# FAN-zero30-SHIM.net
KiCad netlist of a schematic drawn in EAGLE
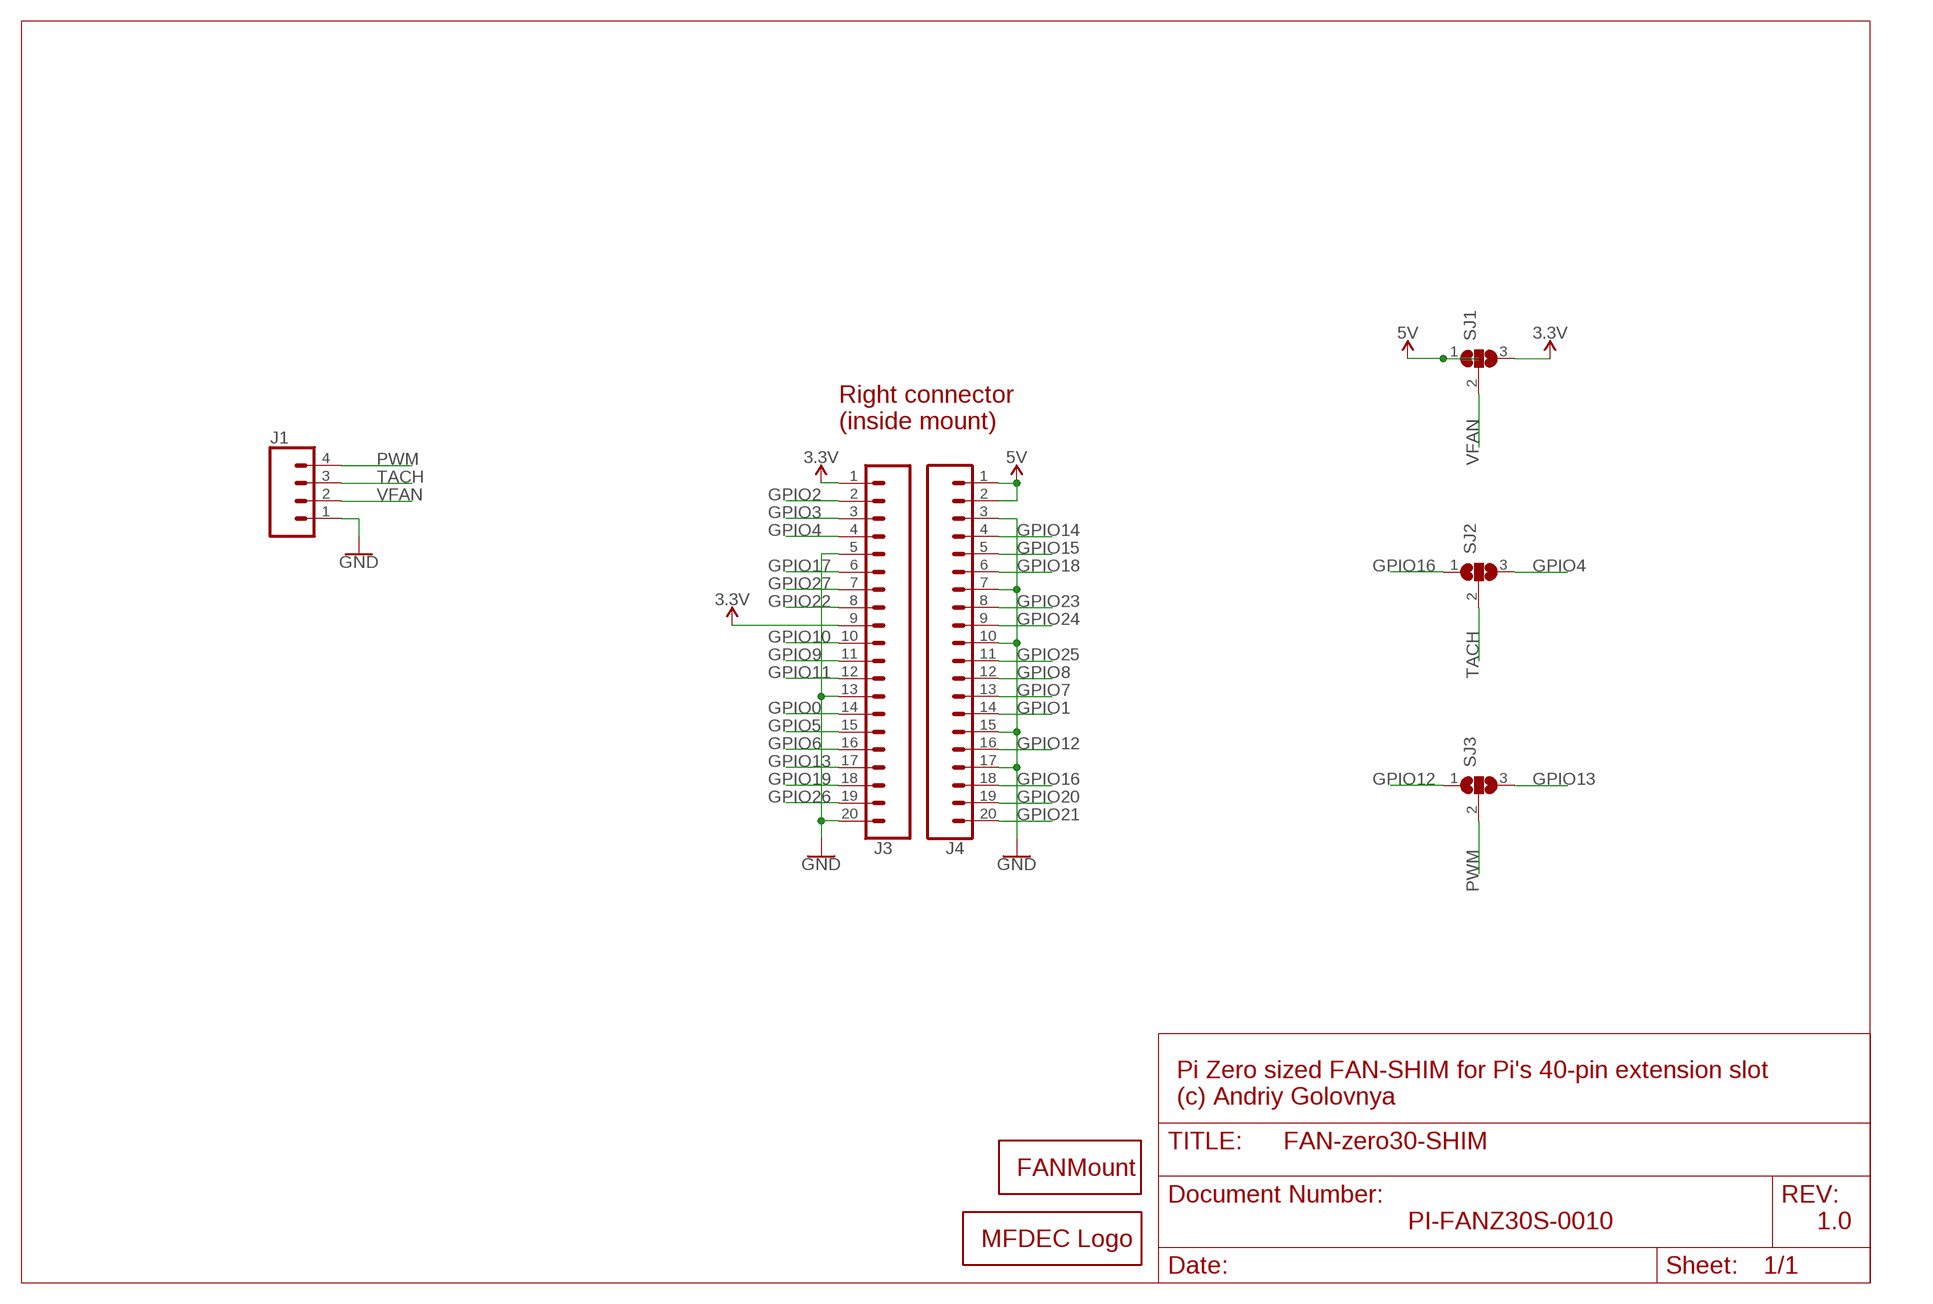
[diagram p0: schematic, sheet 1]

(export (version "E")
  (design (tool "Eeschema 10.0.6"))
  (components
    (comp (ref "FAN1")
      (value "FAN30HO")
      (footprint "eagle-import:FAN30HO")
      (libsource (lib "eagle-import") (part "FAN30HO"))
    )
    (comp (ref "J1")
      (value "CONN_04")
      (footprint "eagle-import:1X04")
      (libsource (lib "eagle-import") (part "CONN_04"))
    )
    (comp (ref "J3")
      (value "CONN_20LOCK")
      (footprint "eagle-import:1X20_LOCK")
      (libsource (lib "eagle-import") (part "CONN_20LOCK"))
    )
    (comp (ref "J4")
      (value "CONN_20LOCK")
      (footprint "eagle-import:1X20_LOCK")
      (libsource (lib "eagle-import") (part "CONN_20LOCK"))
    )
    (comp (ref "LOGO1")
      (value "MFDECLOGO_L_30MM")
      (footprint "eagle-import:MFDEC_L_30MM")
      (libsource (lib "eagle-import") (part "MFDECLOGO_L_30MM"))
    )
    (comp (ref "SJ1")
      (value "SJ2")
      (footprint "eagle-import:SJ_2")
      (libsource (lib "eagle-import") (part "SJ2"))
    )
    (comp (ref "SJ2")
      (value "SJ2")
      (footprint "eagle-import:SJ_2")
      (libsource (lib "eagle-import") (part "SJ2"))
    )
    (comp (ref "SJ3")
      (value "SJ2")
      (footprint "eagle-import:SJ_2")
      (libsource (lib "eagle-import") (part "SJ2"))
    )
  )
  (nets
    (net (code "1") (name "/GPIO0") (class "Default")
      (node (ref "J3") (pin "14") (pinfunction "14_14") (pintype "passive"))
    )
    (net (code "2") (name "/GPIO1") (class "Default")
      (node (ref "J4") (pin "14") (pinfunction "14_14") (pintype "passive"))
    )
    (net (code "3") (name "/GPIO2") (class "Default")
      (node (ref "J3") (pin "2") (pinfunction "2_2") (pintype "passive"))
    )
    (net (code "4") (name "/GPIO3") (class "Default")
      (node (ref "J3") (pin "3") (pinfunction "3_3") (pintype "passive"))
    )
    (net (code "5") (name "/GPIO4") (class "Default")
      (node (ref "J3") (pin "4") (pinfunction "4_4") (pintype "passive"))
      (node (ref "SJ2") (pin "3") (pinfunction "3_3") (pintype "passive"))
    )
    (net (code "6") (name "/GPIO5") (class "Default")
      (node (ref "J3") (pin "15") (pinfunction "15_15") (pintype "passive"))
    )
    (net (code "7") (name "/GPIO6") (class "Default")
      (node (ref "J3") (pin "16") (pinfunction "16_16") (pintype "passive"))
    )
    (net (code "8") (name "/GPIO7") (class "Default")
      (node (ref "J4") (pin "13") (pinfunction "13_13") (pintype "passive"))
    )
    (net (code "9") (name "/GPIO8") (class "Default")
      (node (ref "J4") (pin "12") (pinfunction "12_12") (pintype "passive"))
    )
    (net (code "10") (name "/GPIO9") (class "Default")
      (node (ref "J3") (pin "11") (pinfunction "11_11") (pintype "passive"))
    )
    (net (code "11") (name "/GPIO10") (class "Default")
      (node (ref "J3") (pin "10") (pinfunction "10_10") (pintype "passive"))
    )
    (net (code "12") (name "/GPIO11") (class "Default")
      (node (ref "J3") (pin "12") (pinfunction "12_12") (pintype "passive"))
    )
    (net (code "13") (name "/GPIO12") (class "Default")
      (node (ref "J4") (pin "16") (pinfunction "16_16") (pintype "passive"))
      (node (ref "SJ3") (pin "1") (pinfunction "1_1") (pintype "passive"))
    )
    (net (code "14") (name "/GPIO13") (class "Default")
      (node (ref "J3") (pin "17") (pinfunction "17_17") (pintype "passive"))
      (node (ref "SJ3") (pin "3") (pinfunction "3_3") (pintype "passive"))
    )
    (net (code "15") (name "/GPIO14") (class "Default")
      (node (ref "J4") (pin "4") (pinfunction "4_4") (pintype "passive"))
    )
    (net (code "16") (name "/GPIO15") (class "Default")
      (node (ref "J4") (pin "5") (pinfunction "5_5") (pintype "passive"))
    )
    (net (code "17") (name "/GPIO16") (class "Default")
      (node (ref "J4") (pin "18") (pinfunction "18_18") (pintype "passive"))
      (node (ref "SJ2") (pin "1") (pinfunction "1_1") (pintype "passive"))
    )
    (net (code "18") (name "/GPIO17") (class "Default")
      (node (ref "J3") (pin "6") (pinfunction "6_6") (pintype "passive"))
    )
    (net (code "19") (name "/GPIO18") (class "Default")
      (node (ref "J4") (pin "6") (pinfunction "6_6") (pintype "passive"))
    )
    (net (code "20") (name "/GPIO19") (class "Default")
      (node (ref "J3") (pin "18") (pinfunction "18_18") (pintype "passive"))
    )
    (net (code "21") (name "/GPIO20") (class "Default")
      (node (ref "J4") (pin "19") (pinfunction "19_19") (pintype "passive"))
    )
    (net (code "22") (name "/GPIO21") (class "Default")
      (node (ref "J4") (pin "20") (pinfunction "20_20") (pintype "passive"))
    )
    (net (code "23") (name "/GPIO22") (class "Default")
      (node (ref "J3") (pin "8") (pinfunction "8_8") (pintype "passive"))
    )
    (net (code "24") (name "/GPIO23") (class "Default")
      (node (ref "J4") (pin "8") (pinfunction "8_8") (pintype "passive"))
    )
    (net (code "25") (name "/GPIO24") (class "Default")
      (node (ref "J4") (pin "9") (pinfunction "9_9") (pintype "passive"))
    )
    (net (code "26") (name "/GPIO25") (class "Default")
      (node (ref "J4") (pin "11") (pinfunction "11_11") (pintype "passive"))
    )
    (net (code "27") (name "/GPIO26") (class "Default")
      (node (ref "J3") (pin "19") (pinfunction "19_19") (pintype "passive"))
    )
    (net (code "28") (name "/GPIO27") (class "Default")
      (node (ref "J3") (pin "7") (pinfunction "7_7") (pintype "passive"))
    )
    (net (code "29") (name "/PWM") (class "Default")
      (node (ref "J1") (pin "4") (pinfunction "4_4") (pintype "passive"))
      (node (ref "SJ3") (pin "2") (pinfunction "2_2") (pintype "passive"))
    )
    (net (code "30") (name "/TACH") (class "Default")
      (node (ref "J1") (pin "3") (pinfunction "3_3") (pintype "passive"))
      (node (ref "SJ2") (pin "2") (pinfunction "2_2") (pintype "passive"))
    )
    (net (code "31") (name "/VFAN") (class "Default")
      (node (ref "J1") (pin "2") (pinfunction "2_2") (pintype "passive"))
      (node (ref "SJ1") (pin "2") (pinfunction "2_2") (pintype "passive"))
    )
    (net (code "32") (name "3.3V") (class "Default")
      (node (ref "J3") (pin "1") (pinfunction "1_1") (pintype "passive"))
      (node (ref "J3") (pin "9") (pinfunction "9_9") (pintype "passive"))
      (node (ref "SJ1") (pin "3") (pinfunction "3_3") (pintype "passive"))
    )
    (net (code "33") (name "5V") (class "Default")
      (node (ref "J4") (pin "1") (pinfunction "1_1") (pintype "passive"))
      (node (ref "J4") (pin "2") (pinfunction "2_2") (pintype "passive"))
      (node (ref "SJ1") (pin "1") (pinfunction "1_1") (pintype "passive"))
    )
    (net (code "34") (name "GND") (class "Default")
      (node (ref "J1") (pin "1") (pinfunction "1_1") (pintype "passive"))
      (node (ref "J3") (pin "13") (pinfunction "13_13") (pintype "passive"))
      (node (ref "J3") (pin "20") (pinfunction "20_20") (pintype "passive"))
      (node (ref "J3") (pin "5") (pinfunction "5_5") (pintype "passive"))
      (node (ref "J4") (pin "10") (pinfunction "10_10") (pintype "passive"))
      (node (ref "J4") (pin "15") (pinfunction "15_15") (pintype "passive"))
      (node (ref "J4") (pin "17") (pinfunction "17_17") (pintype "passive"))
      (node (ref "J4") (pin "3") (pinfunction "3_3") (pintype "passive"))
      (node (ref "J4") (pin "7") (pinfunction "7_7") (pintype "passive"))
    )
  )
)
